# Sensor_Interface.net
KiCad netlist of a schematic drawn in Altium Designer
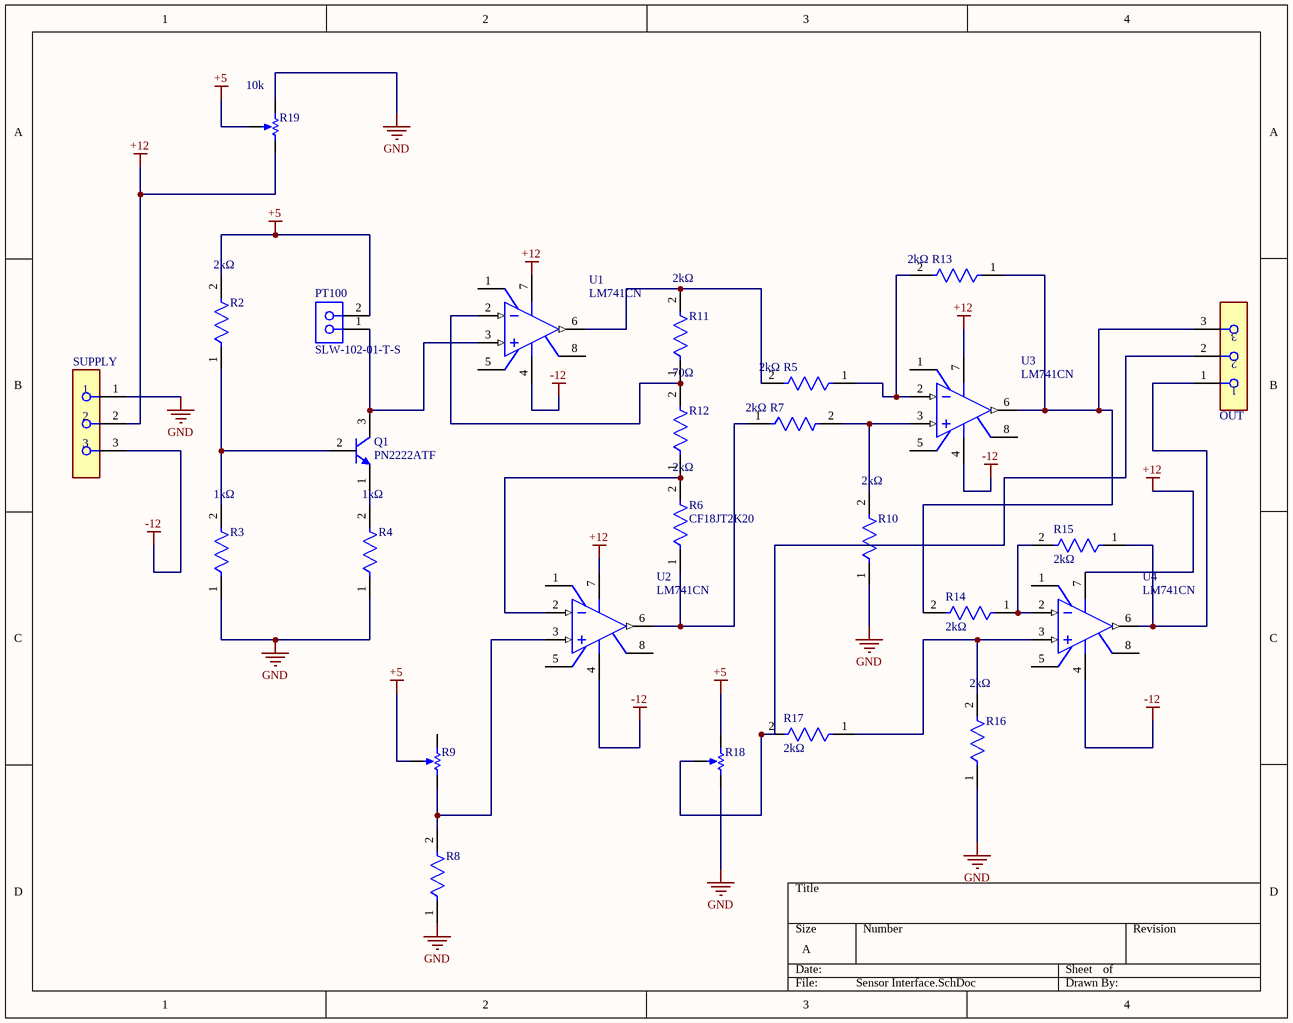
[diagram p0: Sensor Interface.SchDoc]

(export (version "E")
  (design (tool "Eeschema 10.0.6"))
  (components
    (comp (ref "OUT")
      (value "SSQ-103-01-T-S")
      (footprint "FP-SSQ-103-01-T-S-MFG")
      (description "CONN RCPT 3POS 0.1 TIN PCB")
      (libsource (lib "") (part "9e3c5d0b45d2cf0495be8a0529c1856_1"))
    )
    (comp (ref "PT100")
      (value "SLW-102-01-T-S")
      (footprint "SMTC-SLW-102-01-X-S")
      (fields (field (name "MANUFACTURER") "Samtec"))
      (libsource (lib "Altium Content Vault") (part "SMTC-SLW-102-01-X-S"))
    )
    (comp (ref "Q1")
      (value "PN2222ATF")
      (footprint "FAIR-TO-92-3")
      (description "NPN General-Purpose Amplifier, 40 V, -55 to 150 degC, 3-Pin TO-92, RoHS, Tape and Reel")
      (fields (field (name "MANUFACTURER") "FairchildSemiconductor"))
      (libsource (lib "Altium Content Vault") (part "BJT-NPN-EBC-3"))
    )
    (comp (ref "R2")
      (value "CF18JT2K20")
      (footprint "FP-CF18-MFG")
      (description "RES 2.2K OHM 1/8W 5% CF AXIAL")
      (fields
        (field (name "OCTOPART") "https://octopart.com/cf18jt2k20-stackpole+electronics-19205714")
        (field (name "TOLERANCE") "5%")
        (field (name "RESISTANCE") "2kΩ")
      )
      (libsource (lib "Altium Content Vault") (part "1029c3af85768c4190bb7ad29bc67b5"))
    )
    (comp (ref "R3")
      (value "CF18JT2K20")
      (footprint "FP-CF18-MFG")
      (description "RES 2.2K OHM 1/8W 5% CF AXIAL")
      (fields
        (field (name "OCTOPART") "https://octopart.com/cf18jt2k20-stackpole+electronics-19205714")
        (field (name "TOLERANCE") "5%")
        (field (name "RESISTANCE") "1kΩ")
      )
      (libsource (lib "Altium Content Vault") (part "1029c3af85768c4190bb7ad29bc67b5"))
    )
    (comp (ref "R4")
      (value "1kΩ")
      (footprint "FP-CF18-MFG")
      (description "RES 2.2K OHM 1/8W 5% CF AXIAL")
      (fields
        (field (name "OCTOPART") "https://octopart.com/cf18jt2k20-stackpole+electronics-19205714")
        (field (name "TOLERANCE") "5%")
      )
      (libsource (lib "Altium Content Vault") (part "1029c3af85768c4190bb7ad29bc67b5"))
    )
    (comp (ref "R5")
      (value "CF18JT2K20")
      (footprint "FP-CF18-MFG")
      (description "RES 2.2K OHM 1/8W 5% CF AXIAL")
      (fields
        (field (name "OCTOPART") "https://octopart.com/cf18jt2k20-stackpole+electronics-19205714")
        (field (name "TOLERANCE") "5%")
        (field (name "RESISTANCE") "2kΩ")
      )
      (libsource (lib "Altium Content Vault") (part "1029c3af85768c4190bb7ad29bc67b5"))
    )
    (comp (ref "R6")
      (value "CF18JT2K20")
      (footprint "FP-CF18-MFG")
      (description "RES 2.2K OHM 1/8W 5% CF AXIAL")
      (fields
        (field (name "OCTOPART") "https://octopart.com/cf18jt2k20-stackpole+electronics-19205714")
        (field (name "TOLERANCE") "5%")
        (field (name "RESISTANCE") "2kΩ")
      )
      (libsource (lib "Altium Content Vault") (part "1029c3af85768c4190bb7ad29bc67b5"))
    )
    (comp (ref "R7")
      (value "CF18JT2K20")
      (footprint "FP-CF18-MFG")
      (description "RES 2.2K OHM 1/8W 5% CF AXIAL")
      (fields
        (field (name "OCTOPART") "https://octopart.com/cf18jt2k20-stackpole+electronics-19205714")
        (field (name "TOLERANCE") "5%")
        (field (name "RESISTANCE") "2kΩ")
      )
      (libsource (lib "Altium Content Vault") (part "1029c3af85768c4190bb7ad29bc67b5"))
    )
    (comp (ref "R8")
      (value "CF18JT2K20")
      (footprint "FP-CF18-MFG")
      (description "RES 2.2K OHM 1/8W 5% CF AXIAL")
      (fields
        (field (name "OCTOPART") "https://octopart.com/cf18jt2k20-stackpole+electronics-19205714")
        (field (name "TOLERANCE") "5%")
      )
      (libsource (lib "Altium Content Vault") (part "1029c3af85768c4190bb7ad29bc67b5"))
    )
    (comp (ref "R9")
      (value "3362P-1-104LF")
      (footprint "BOUR-3362P")
      (description "Square Trimpot(R) Trimming Potentiometer, 100 KOhm, 300 V, -55 to 125 degC, 3-Pin THD, RoHS, Tube")
      (fields (field (name "TOLERANCE") "1%"))
      (libsource (lib "Altium Content Vault") (part "RES-POT-3"))
    )
    (comp (ref "R10")
      (value "CF18JT2K20")
      (footprint "FP-CF18-MFG")
      (description "RES 2.2K OHM 1/8W 5% CF AXIAL")
      (fields
        (field (name "OCTOPART") "https://octopart.com/cf18jt2k20-stackpole+electronics-19205714")
        (field (name "TOLERANCE") "5%")
        (field (name "RESISTANCE") "2kΩ")
      )
      (libsource (lib "Altium Content Vault") (part "1029c3af85768c4190bb7ad29bc67b5"))
    )
    (comp (ref "R11")
      (value "CF18JT2K20")
      (footprint "FP-CF18-MFG")
      (description "RES 2.2K OHM 1/8W 5% CF AXIAL")
      (fields
        (field (name "OCTOPART") "https://octopart.com/cf18jt2k20-stackpole+electronics-19205714")
        (field (name "TOLERANCE") "5%")
        (field (name "RESISTANCE") "2kΩ")
      )
      (libsource (lib "Altium Content Vault") (part "1029c3af85768c4190bb7ad29bc67b5"))
    )
    (comp (ref "R12")
      (value "CF18JT2K20")
      (footprint "FP-CF18-MFG")
      (description "RES 2.2K OHM 1/8W 5% CF AXIAL")
      (fields
        (field (name "OCTOPART") "https://octopart.com/cf18jt2k20-stackpole+electronics-19205714")
        (field (name "TOLERANCE") "5%")
        (field (name "RESISTANCE") "70Ω")
      )
      (libsource (lib "Altium Content Vault") (part "1029c3af85768c4190bb7ad29bc67b5"))
    )
    (comp (ref "R13")
      (value "CF18JT2K20")
      (footprint "FP-CF18-MFG")
      (description "RES 2.2K OHM 1/8W 5% CF AXIAL")
      (fields
        (field (name "OCTOPART") "https://octopart.com/cf18jt2k20-stackpole+electronics-19205714")
        (field (name "TOLERANCE") "5%")
        (field (name "RESISTANCE") "2kΩ")
      )
      (libsource (lib "Altium Content Vault") (part "1029c3af85768c4190bb7ad29bc67b5"))
    )
    (comp (ref "R14")
      (value "CF18JT2K20")
      (footprint "FP-CF18-MFG")
      (description "RES 2.2K OHM 1/8W 5% CF AXIAL")
      (fields
        (field (name "OCTOPART") "https://octopart.com/cf18jt2k20-stackpole+electronics-19205714")
        (field (name "TOLERANCE") "5%")
        (field (name "RESISTANCE") "2kΩ")
      )
      (libsource (lib "Altium Content Vault") (part "1029c3af85768c4190bb7ad29bc67b5"))
    )
    (comp (ref "R15")
      (value "CF18JT2K20")
      (footprint "FP-CF18-MFG")
      (description "RES 2.2K OHM 1/8W 5% CF AXIAL")
      (fields
        (field (name "OCTOPART") "https://octopart.com/cf18jt2k20-stackpole+electronics-19205714")
        (field (name "TOLERANCE") "5%")
        (field (name "RESISTANCE") "2kΩ")
      )
      (libsource (lib "Altium Content Vault") (part "1029c3af85768c4190bb7ad29bc67b5"))
    )
    (comp (ref "R16")
      (value "CF18JT2K20")
      (footprint "FP-CF18-MFG")
      (description "RES 2.2K OHM 1/8W 5% CF AXIAL")
      (fields
        (field (name "OCTOPART") "https://octopart.com/cf18jt2k20-stackpole+electronics-19205714")
        (field (name "TOLERANCE") "5%")
        (field (name "RESISTANCE") "2kΩ")
      )
      (libsource (lib "Altium Content Vault") (part "1029c3af85768c4190bb7ad29bc67b5"))
    )
    (comp (ref "R17")
      (value "CF18JT2K20")
      (footprint "FP-CF18-MFG")
      (description "RES 2.2K OHM 1/8W 5% CF AXIAL")
      (fields
        (field (name "OCTOPART") "https://octopart.com/cf18jt2k20-stackpole+electronics-19205714")
        (field (name "TOLERANCE") "5%")
        (field (name "RESISTANCE") "2kΩ")
      )
      (libsource (lib "Altium Content Vault") (part "1029c3af85768c4190bb7ad29bc67b5"))
    )
    (comp (ref "R18")
      (value "3362P-1-104LF")
      (footprint "BOUR-3362P")
      (description "Square Trimpot(R) Trimming Potentiometer, 100 KOhm, 300 V, -55 to 125 degC, 3-Pin THD, RoHS, Tube")
      (fields (field (name "TOLERANCE") "1%"))
      (libsource (lib "Altium Content Vault") (part "RES-POT-3"))
    )
    (comp (ref "R19")
      (value "3362P-1-104LF")
      (footprint "BOUR-3362P")
      (description "Square Trimpot(R) Trimming Potentiometer, 100 KOhm, 300 V, -55 to 125 degC, 3-Pin THD, RoHS, Tube")
      (fields (field (name "TOLERANCE") "1%") (field (name "RESISTANCE") "10k"))
      (libsource (lib "Altium Content Vault") (part "RES-POT-3"))
    )
    (comp (ref "SUPPLY")
      (value "SSQ-103-01-T-S")
      (footprint "FP-SSQ-103-01-T-S-MFG")
      (description "CONN RCPT 3POS 0.1 TIN PCB")
      (libsource (lib "Altium Content Vault") (part "9e3c5d0b45d2cf0495be8a0529c1856"))
    )
    (comp (ref "U1")
      (value "LM741CN")
      (footprint "N08E")
      (description "Operational Amplifier, 8-pin MDIP")
      (fields (field (name "MANUFACTURER") "National Semiconductor"))
      (libsource (lib "Altium Content Vault") (part "AMP-OPA-LM741-8"))
    )
    (comp (ref "U2")
      (value "LM741CN")
      (footprint "N08E")
      (description "Operational Amplifier, 8-pin MDIP")
      (fields (field (name "MANUFACTURER") "National Semiconductor"))
      (libsource (lib "Altium Content Vault") (part "AMP-OPA-LM741-8"))
    )
    (comp (ref "U3")
      (value "LM741CN")
      (footprint "N08E")
      (description "Operational Amplifier, 8-pin MDIP")
      (fields (field (name "MANUFACTURER") "National Semiconductor"))
      (libsource (lib "Altium Content Vault") (part "AMP-OPA-LM741-8"))
    )
    (comp (ref "U4")
      (value "LM741CN")
      (footprint "N08E")
      (description "Operational Amplifier, 8-pin MDIP")
      (fields (field (name "MANUFACTURER") "National Semiconductor"))
      (libsource (lib "Altium Content Vault") (part "AMP-OPA-LM741-8"))
    )
  )
  (nets
    (net (code "1") (name "+5") (class "Default")
      (node (ref "PT100") (pin "2") (pinfunction "2_2") (pintype "passive"))
      (node (ref "R18") (pin "1") (pinfunction "CCW_1") (pintype "passive"))
      (node (ref "R19") (pin "2") (pinfunction "S_2") (pintype "passive"))
      (node (ref "R2") (pin "2") (pinfunction "2_2") (pintype "passive"))
      (node (ref "R9") (pin "2") (pinfunction "S_2") (pintype "passive"))
    )
    (net (code "2") (name "+12") (class "Default")
      (node (ref "R19") (pin "3") (pinfunction "CW_3") (pintype "passive"))
      (node (ref "SUPPLY") (pin "2") (pinfunction "2_2") (pintype "passive"))
      (node (ref "U1") (pin "7") (pinfunction "V+_7") (pintype "power_in"))
      (node (ref "U2") (pin "7") (pinfunction "V+_7") (pintype "power_in"))
      (node (ref "U3") (pin "7") (pinfunction "V+_7") (pintype "power_in"))
      (node (ref "U4") (pin "7") (pinfunction "V+_7") (pintype "power_in"))
    )
    (net (code "3") (name "-12") (class "Default")
      (node (ref "SUPPLY") (pin "3") (pinfunction "3_3") (pintype "passive"))
      (node (ref "U1") (pin "4") (pinfunction "V-_4") (pintype "power_in"))
      (node (ref "U2") (pin "4") (pinfunction "V-_4") (pintype "power_in"))
      (node (ref "U3") (pin "4") (pinfunction "V-_4") (pintype "power_in"))
      (node (ref "U4") (pin "4") (pinfunction "V-_4") (pintype "power_in"))
    )
    (net (code "4") (name "GND") (class "Default")
      (node (ref "R10") (pin "1") (pinfunction "1_1") (pintype "passive"))
      (node (ref "R16") (pin "1") (pinfunction "1_1") (pintype "passive"))
      (node (ref "R18") (pin "3") (pinfunction "CW_3") (pintype "passive"))
      (node (ref "R19") (pin "1") (pinfunction "CCW_1") (pintype "passive"))
      (node (ref "R3") (pin "1") (pinfunction "1_1") (pintype "passive"))
      (node (ref "R4") (pin "1") (pinfunction "1_1") (pintype "passive"))
      (node (ref "R8") (pin "1") (pinfunction "1_1") (pintype "passive"))
      (node (ref "SUPPLY") (pin "1") (pinfunction "1_1") (pintype "passive"))
    )
    (net (code "5") (name "Net-(Q1-B)") (class "Default")
      (node (ref "Q1") (pin "2") (pinfunction "B_2") (pintype "passive"))
      (node (ref "R2") (pin "1") (pinfunction "1_1") (pintype "passive"))
      (node (ref "R3") (pin "2") (pinfunction "2_2") (pintype "passive"))
    )
    (net (code "6") (name "Net-(Q1-C)") (class "Default")
      (node (ref "PT100") (pin "1") (pinfunction "1_1") (pintype "passive"))
      (node (ref "Q1") (pin "3") (pinfunction "C_3") (pintype "passive"))
      (node (ref "U1") (pin "3") (pinfunction "IN+_3") (pintype "input"))
    )
    (net (code "7") (name "Net-(Q1-E)") (class "Default")
      (node (ref "Q1") (pin "1") (pinfunction "E_1") (pintype "passive"))
      (node (ref "R4") (pin "2") (pinfunction "2_2") (pintype "passive"))
    )
    (net (code "8") (name "Net-(R9-CW)") (class "Default")
      (node (ref "R8") (pin "2") (pinfunction "2_2") (pintype "passive"))
      (node (ref "R9") (pin "3") (pinfunction "CW_3") (pintype "passive"))
      (node (ref "U2") (pin "3") (pinfunction "IN+_3") (pintype "input"))
    )
    (net (code "9") (name "Net-(R18-S)") (class "Default")
      (node (ref "OUT") (pin "2") (pinfunction "2_2") (pintype "passive"))
      (node (ref "R17") (pin "2") (pinfunction "2_2") (pintype "passive"))
      (node (ref "R18") (pin "2") (pinfunction "S_2") (pintype "passive"))
    )
    (net (code "10") (name "Net-(U1-IN-)") (class "Default")
      (node (ref "R11") (pin "1") (pinfunction "1_1") (pintype "passive"))
      (node (ref "R12") (pin "2") (pinfunction "2_2") (pintype "passive"))
      (node (ref "U1") (pin "2") (pinfunction "IN-_2") (pintype "input"))
    )
    (net (code "11") (name "Net-(U1-OUT)") (class "Default")
      (node (ref "R11") (pin "2") (pinfunction "2_2") (pintype "passive"))
      (node (ref "R5") (pin "2") (pinfunction "2_2") (pintype "passive"))
      (node (ref "U1") (pin "6") (pinfunction "OUT_6") (pintype "output"))
    )
    (net (code "12") (name "Net-(U2-IN-)") (class "Default")
      (node (ref "R12") (pin "1") (pinfunction "1_1") (pintype "passive"))
      (node (ref "R6") (pin "2") (pinfunction "2_2") (pintype "passive"))
      (node (ref "U2") (pin "2") (pinfunction "IN-_2") (pintype "input"))
    )
    (net (code "13") (name "Net-(U2-OUT)") (class "Default")
      (node (ref "R6") (pin "1") (pinfunction "1_1") (pintype "passive"))
      (node (ref "R7") (pin "1") (pinfunction "1_1") (pintype "passive"))
      (node (ref "U2") (pin "6") (pinfunction "OUT_6") (pintype "output"))
    )
    (net (code "14") (name "Net-(U3-IN+)") (class "Default")
      (node (ref "R10") (pin "2") (pinfunction "2_2") (pintype "passive"))
      (node (ref "R7") (pin "2") (pinfunction "2_2") (pintype "passive"))
      (node (ref "U3") (pin "3") (pinfunction "IN+_3") (pintype "input"))
    )
    (net (code "15") (name "Net-(U3-IN-)") (class "Default")
      (node (ref "R13") (pin "2") (pinfunction "2_2") (pintype "passive"))
      (node (ref "R5") (pin "1") (pinfunction "1_1") (pintype "passive"))
      (node (ref "U3") (pin "2") (pinfunction "IN-_2") (pintype "input"))
    )
    (net (code "16") (name "Net-(U3-OUT)") (class "Default")
      (node (ref "OUT") (pin "3") (pinfunction "3_3") (pintype "passive"))
      (node (ref "R13") (pin "1") (pinfunction "1_1") (pintype "passive"))
      (node (ref "R14") (pin "2") (pinfunction "2_2") (pintype "passive"))
      (node (ref "U3") (pin "6") (pinfunction "OUT_6") (pintype "output"))
    )
    (net (code "17") (name "Net-(U4-IN+)") (class "Default")
      (node (ref "R16") (pin "2") (pinfunction "2_2") (pintype "passive"))
      (node (ref "R17") (pin "1") (pinfunction "1_1") (pintype "passive"))
      (node (ref "U4") (pin "3") (pinfunction "IN+_3") (pintype "input"))
    )
    (net (code "18") (name "Net-(U4-IN-)") (class "Default")
      (node (ref "R14") (pin "1") (pinfunction "1_1") (pintype "passive"))
      (node (ref "R15") (pin "2") (pinfunction "2_2") (pintype "passive"))
      (node (ref "U4") (pin "2") (pinfunction "IN-_2") (pintype "input"))
    )
    (net (code "19") (name "Net-(U4-OUT)") (class "Default")
      (node (ref "OUT") (pin "1") (pinfunction "1_1") (pintype "passive"))
      (node (ref "R15") (pin "1") (pinfunction "1_1") (pintype "passive"))
      (node (ref "U4") (pin "6") (pinfunction "OUT_6") (pintype "output"))
    )
    (net (code "20") (name "unconnected-(R9-CCW-Pad1)") (class "Default")
      (node (ref "R9") (pin "1") (pinfunction "CCW_1") (pintype "passive"))
    )
    (net (code "21") (name "unconnected-(U1-NC-Pad8)") (class "Default")
      (node (ref "U1") (pin "8") (pinfunction "NC_8") (pintype "passive"))
    )
    (net (code "22") (name "unconnected-(U1-OFS_NULL-Pad1)") (class "Default")
      (node (ref "U1") (pin "1") (pinfunction "OFS_NULL_1") (pintype "passive"))
    )
    (net (code "23") (name "unconnected-(U1-OFS_NULL-Pad5)") (class "Default")
      (node (ref "U1") (pin "5") (pinfunction "OFS_NULL_5") (pintype "passive"))
    )
    (net (code "24") (name "unconnected-(U2-NC-Pad8)") (class "Default")
      (node (ref "U2") (pin "8") (pinfunction "NC_8") (pintype "passive"))
    )
    (net (code "25") (name "unconnected-(U2-OFS_NULL-Pad1)") (class "Default")
      (node (ref "U2") (pin "1") (pinfunction "OFS_NULL_1") (pintype "passive"))
    )
    (net (code "26") (name "unconnected-(U2-OFS_NULL-Pad5)") (class "Default")
      (node (ref "U2") (pin "5") (pinfunction "OFS_NULL_5") (pintype "passive"))
    )
    (net (code "27") (name "unconnected-(U3-NC-Pad8)") (class "Default")
      (node (ref "U3") (pin "8") (pinfunction "NC_8") (pintype "passive"))
    )
    (net (code "28") (name "unconnected-(U3-OFS_NULL-Pad1)") (class "Default")
      (node (ref "U3") (pin "1") (pinfunction "OFS_NULL_1") (pintype "passive"))
    )
    (net (code "29") (name "unconnected-(U3-OFS_NULL-Pad5)") (class "Default")
      (node (ref "U3") (pin "5") (pinfunction "OFS_NULL_5") (pintype "passive"))
    )
    (net (code "30") (name "unconnected-(U4-NC-Pad8)") (class "Default")
      (node (ref "U4") (pin "8") (pinfunction "NC_8") (pintype "passive"))
    )
    (net (code "31") (name "unconnected-(U4-OFS_NULL-Pad1)") (class "Default")
      (node (ref "U4") (pin "1") (pinfunction "OFS_NULL_1") (pintype "passive"))
    )
    (net (code "32") (name "unconnected-(U4-OFS_NULL-Pad5)") (class "Default")
      (node (ref "U4") (pin "5") (pinfunction "OFS_NULL_5") (pintype "passive"))
    )
  )
)
